# shield.net
KiCad netlist of a schematic drawn in EAGLE
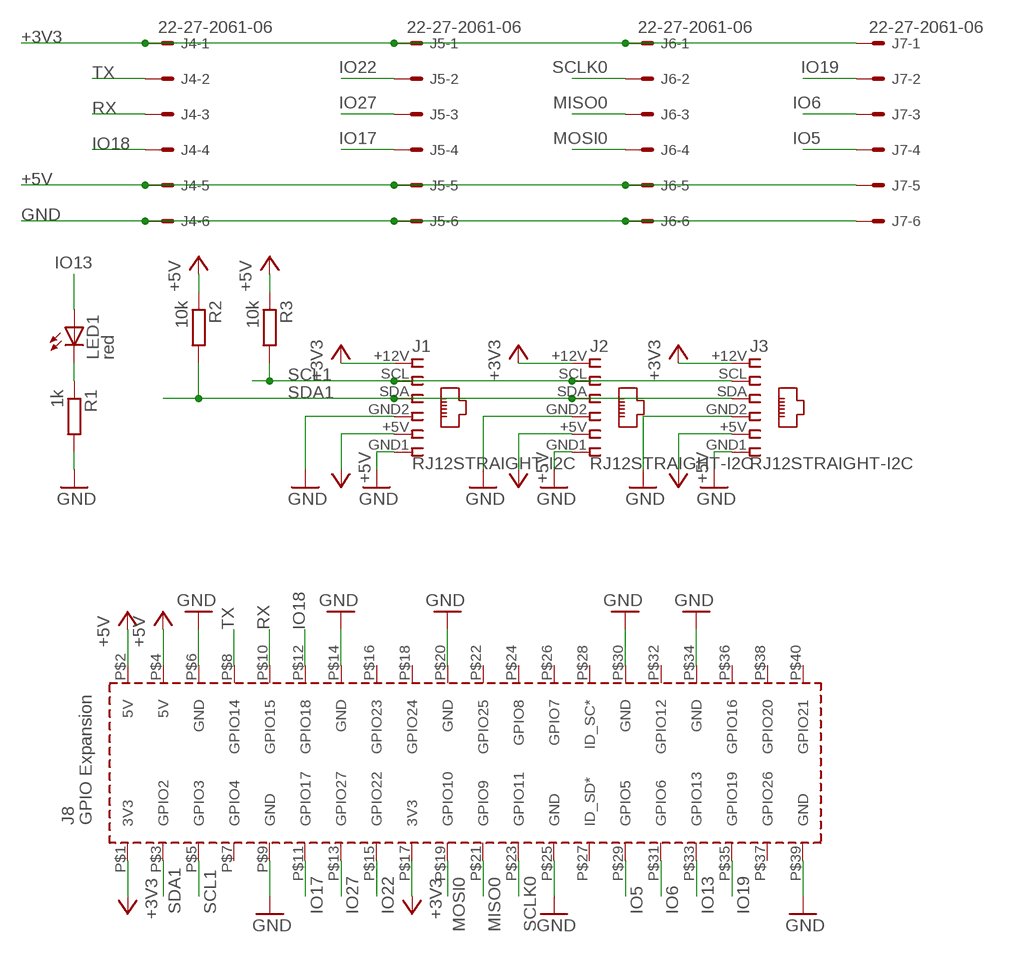
[diagram p0: schematic, sheet 1]

(export (version "E")
  (design (tool "Eeschema 10.0.6"))
  (components
    (comp (ref "J1")
      (value "RJ12STRAIGHT-I2C")
      (footprint "eagle-import:RJ12-STRAIGHT-I2C")
      (libsource (lib "eagle-import") (part "RJ12STRAIGHT-I2C"))
    )
    (comp (ref "J2")
      (value "RJ12STRAIGHT-I2C")
      (footprint "eagle-import:RJ12-STRAIGHT-I2C")
      (libsource (lib "eagle-import") (part "RJ12STRAIGHT-I2C"))
    )
    (comp (ref "J3")
      (value "RJ12STRAIGHT-I2C")
      (footprint "eagle-import:RJ12-STRAIGHT-I2C")
      (libsource (lib "eagle-import") (part "RJ12STRAIGHT-I2C"))
    )
    (comp (ref "J4")
      (value "22-27-2061-06")
      (footprint "eagle-import:6410-06")
      (fields (field (name "MF") "MOLEX"))
      (libsource (lib "eagle-import") (part "22-?-0627-2061"))
    )
    (comp (ref "J5")
      (value "22-27-2061-06")
      (footprint "eagle-import:6410-06")
      (fields (field (name "MF") "MOLEX"))
      (libsource (lib "eagle-import") (part "22-?-0627-2061"))
    )
    (comp (ref "J6")
      (value "22-27-2061-06")
      (footprint "eagle-import:6410-06")
      (fields (field (name "MF") "MOLEX"))
      (libsource (lib "eagle-import") (part "22-?-0627-2061"))
    )
    (comp (ref "J7")
      (value "22-27-2061-06")
      (footprint "eagle-import:6410-06")
      (fields (field (name "MF") "MOLEX"))
      (libsource (lib "eagle-import") (part "22-?-0627-2061"))
    )
    (comp (ref "LED1")
      (value "red")
      (footprint "eagle-import:SML0805")
      (libsource (lib "eagle-import") (part "LEDSML0805"))
    )
    (comp (ref "PCB1")
      (value "RPI3RPI3MIRROR")
      (footprint "eagle-import:RPI3MIRROR")
      (libsource (lib "eagle-import") (part "RPI3RPI3MIRROR"))
    )
    (comp (ref "R1")
      (value "1k")
      (footprint "eagle-import:R0805")
      (libsource (lib "eagle-import") (part "R-EU_R0805"))
    )
    (comp (ref "R2")
      (value "10k")
      (footprint "eagle-import:R0805")
      (libsource (lib "eagle-import") (part "R-EU_R0805"))
    )
    (comp (ref "R3")
      (value "10k")
      (footprint "eagle-import:R0805")
      (libsource (lib "eagle-import") (part "R-EU_R0805"))
    )
  )
  (nets
    (net (code "1") (name "+3V3") (class "Default")
      (node (ref "J1") (pin "+12V") (pinfunction "1_+12V") (pintype "bidirectional"))
      (node (ref "J2") (pin "+12V") (pinfunction "1_+12V") (pintype "bidirectional"))
      (node (ref "J3") (pin "+12V") (pinfunction "1_+12V") (pintype "bidirectional"))
      (node (ref "J4") (pin "1") (pinfunction "S_1") (pintype "passive"))
      (node (ref "J5") (pin "1") (pinfunction "S_1") (pintype "passive"))
      (node (ref "J6") (pin "1") (pinfunction "S_1") (pintype "passive"))
      (node (ref "J7") (pin "1") (pinfunction "S_1") (pintype "passive"))
      (node (ref "PCB1") (pin "P$1") (pinfunction "3V3_P$1") (pintype "bidirectional"))
      (node (ref "PCB1") (pin "P$17") (pinfunction "3V3_P$17") (pintype "bidirectional"))
    )
    (net (code "2") (name "+5V") (class "Default")
      (node (ref "J1") (pin "+5V") (pinfunction "5_+5V") (pintype "bidirectional"))
      (node (ref "J2") (pin "+5V") (pinfunction "5_+5V") (pintype "bidirectional"))
      (node (ref "J3") (pin "+5V") (pinfunction "5_+5V") (pintype "bidirectional"))
      (node (ref "J4") (pin "5") (pinfunction "S_5") (pintype "passive"))
      (node (ref "J5") (pin "5") (pinfunction "S_5") (pintype "passive"))
      (node (ref "J6") (pin "5") (pinfunction "S_5") (pintype "passive"))
      (node (ref "J7") (pin "5") (pinfunction "S_5") (pintype "passive"))
      (node (ref "PCB1") (pin "P$2") (pinfunction "5V_P$2") (pintype "bidirectional"))
      (node (ref "PCB1") (pin "P$4") (pinfunction "5V_P$4") (pintype "bidirectional"))
      (node (ref "R2") (pin "1") (pinfunction "1_1") (pintype "passive"))
      (node (ref "R3") (pin "1") (pinfunction "1_1") (pintype "passive"))
    )
    (net (code "3") (name "/IO5") (class "Default")
      (node (ref "J7") (pin "4") (pinfunction "S_4") (pintype "passive"))
      (node (ref "PCB1") (pin "P$29") (pinfunction "GPIO5_P$29") (pintype "bidirectional"))
    )
    (net (code "4") (name "/IO6") (class "Default")
      (node (ref "J7") (pin "3") (pinfunction "S_3") (pintype "passive"))
      (node (ref "PCB1") (pin "P$31") (pinfunction "GPIO6_P$31") (pintype "bidirectional"))
    )
    (net (code "5") (name "/IO13") (class "Default")
      (node (ref "LED1") (pin "A") (pinfunction "A_A") (pintype "passive"))
      (node (ref "PCB1") (pin "P$33") (pinfunction "GPIO13_P$33") (pintype "bidirectional"))
    )
    (net (code "6") (name "/IO17") (class "Default")
      (node (ref "J5") (pin "4") (pinfunction "S_4") (pintype "passive"))
      (node (ref "PCB1") (pin "P$11") (pinfunction "GPIO17_P$11") (pintype "bidirectional"))
    )
    (net (code "7") (name "/IO18") (class "Default")
      (node (ref "J4") (pin "4") (pinfunction "S_4") (pintype "passive"))
      (node (ref "PCB1") (pin "P$12") (pinfunction "GPIO18_P$12") (pintype "bidirectional"))
    )
    (net (code "8") (name "/IO19") (class "Default")
      (node (ref "J7") (pin "2") (pinfunction "S_2") (pintype "passive"))
      (node (ref "PCB1") (pin "P$35") (pinfunction "GPIO19_P$35") (pintype "bidirectional"))
    )
    (net (code "9") (name "/IO22") (class "Default")
      (node (ref "J5") (pin "2") (pinfunction "S_2") (pintype "passive"))
      (node (ref "PCB1") (pin "P$15") (pinfunction "GPIO22_P$15") (pintype "bidirectional"))
    )
    (net (code "10") (name "/IO27") (class "Default")
      (node (ref "J5") (pin "3") (pinfunction "S_3") (pintype "passive"))
      (node (ref "PCB1") (pin "P$13") (pinfunction "GPIO27_P$13") (pintype "bidirectional"))
    )
    (net (code "11") (name "/MISO0") (class "Default")
      (node (ref "J6") (pin "3") (pinfunction "S_3") (pintype "passive"))
      (node (ref "PCB1") (pin "P$21") (pinfunction "GPIO9_P$21") (pintype "bidirectional"))
    )
    (net (code "12") (name "/MOSI0") (class "Default")
      (node (ref "J6") (pin "4") (pinfunction "S_4") (pintype "passive"))
      (node (ref "PCB1") (pin "P$19") (pinfunction "GPIO10_P$19") (pintype "bidirectional"))
    )
    (net (code "13") (name "/RX") (class "Default")
      (node (ref "J4") (pin "3") (pinfunction "S_3") (pintype "passive"))
      (node (ref "PCB1") (pin "P$10") (pinfunction "GPIO15_P$10") (pintype "bidirectional"))
    )
    (net (code "14") (name "/SCL1") (class "Default")
      (node (ref "J1") (pin "SCL") (pinfunction "2_SCL") (pintype "bidirectional"))
      (node (ref "J2") (pin "SCL") (pinfunction "2_SCL") (pintype "bidirectional"))
      (node (ref "J3") (pin "SCL") (pinfunction "2_SCL") (pintype "bidirectional"))
      (node (ref "PCB1") (pin "P$5") (pinfunction "GPIO3_P$5") (pintype "bidirectional"))
      (node (ref "R3") (pin "2") (pinfunction "2_2") (pintype "passive"))
    )
    (net (code "15") (name "/SCLK0") (class "Default")
      (node (ref "J6") (pin "2") (pinfunction "S_2") (pintype "passive"))
      (node (ref "PCB1") (pin "P$23") (pinfunction "GPIO11_P$23") (pintype "bidirectional"))
    )
    (net (code "16") (name "/SDA1") (class "Default")
      (node (ref "J1") (pin "SDA") (pinfunction "3_SDA") (pintype "bidirectional"))
      (node (ref "J2") (pin "SDA") (pinfunction "3_SDA") (pintype "bidirectional"))
      (node (ref "J3") (pin "SDA") (pinfunction "3_SDA") (pintype "bidirectional"))
      (node (ref "PCB1") (pin "P$3") (pinfunction "GPIO2_P$3") (pintype "bidirectional"))
      (node (ref "R2") (pin "2") (pinfunction "2_2") (pintype "passive"))
    )
    (net (code "17") (name "/TX") (class "Default")
      (node (ref "J4") (pin "2") (pinfunction "S_2") (pintype "passive"))
      (node (ref "PCB1") (pin "P$8") (pinfunction "GPIO14_P$8") (pintype "bidirectional"))
    )
    (net (code "18") (name "GND") (class "Default")
      (node (ref "J1") (pin "GND1") (pinfunction "6_GND1") (pintype "bidirectional"))
      (node (ref "J1") (pin "GND2") (pinfunction "4_GND2") (pintype "bidirectional"))
      (node (ref "J2") (pin "GND1") (pinfunction "6_GND1") (pintype "bidirectional"))
      (node (ref "J2") (pin "GND2") (pinfunction "4_GND2") (pintype "bidirectional"))
      (node (ref "J3") (pin "GND1") (pinfunction "6_GND1") (pintype "bidirectional"))
      (node (ref "J3") (pin "GND2") (pinfunction "4_GND2") (pintype "bidirectional"))
      (node (ref "J4") (pin "6") (pinfunction "S_6") (pintype "passive"))
      (node (ref "J5") (pin "6") (pinfunction "S_6") (pintype "passive"))
      (node (ref "J6") (pin "6") (pinfunction "S_6") (pintype "passive"))
      (node (ref "J7") (pin "6") (pinfunction "S_6") (pintype "passive"))
      (node (ref "PCB1") (pin "P$14") (pinfunction "GND_P$14") (pintype "bidirectional"))
      (node (ref "PCB1") (pin "P$20") (pinfunction "GND_P$20") (pintype "bidirectional"))
      (node (ref "PCB1") (pin "P$25") (pinfunction "GND_P$25") (pintype "bidirectional"))
      (node (ref "PCB1") (pin "P$30") (pinfunction "GND_P$30") (pintype "bidirectional"))
      (node (ref "PCB1") (pin "P$34") (pinfunction "GND_P$34") (pintype "bidirectional"))
      (node (ref "PCB1") (pin "P$39") (pinfunction "GND_P$39") (pintype "bidirectional"))
      (node (ref "PCB1") (pin "P$6") (pinfunction "GND_P$6") (pintype "bidirectional"))
      (node (ref "PCB1") (pin "P$9") (pinfunction "GND_P$9") (pintype "bidirectional"))
      (node (ref "R1") (pin "2") (pinfunction "2_2") (pintype "passive"))
    )
    (net (code "19") (name "Net-(LED1-PadC)") (class "Default")
      (node (ref "LED1") (pin "C") (pinfunction "C_C") (pintype "passive"))
      (node (ref "R1") (pin "1") (pinfunction "1_1") (pintype "passive"))
    )
    (net (code "20") (name "unconnected-(PCB1-GPIO4-PadP$7)") (class "Default")
      (node (ref "PCB1") (pin "P$7") (pinfunction "GPIO4_P$7") (pintype "bidirectional"))
    )
    (net (code "21") (name "unconnected-(PCB1-GPIO7-PadP$26)") (class "Default")
      (node (ref "PCB1") (pin "P$26") (pinfunction "GPIO7_P$26") (pintype "bidirectional"))
    )
    (net (code "22") (name "unconnected-(PCB1-GPIO8-PadP$24)") (class "Default")
      (node (ref "PCB1") (pin "P$24") (pinfunction "GPIO8_P$24") (pintype "bidirectional"))
    )
    (net (code "23") (name "unconnected-(PCB1-GPIO12-PadP$32)") (class "Default")
      (node (ref "PCB1") (pin "P$32") (pinfunction "GPIO12_P$32") (pintype "bidirectional"))
    )
    (net (code "24") (name "unconnected-(PCB1-GPIO16-PadP$36)") (class "Default")
      (node (ref "PCB1") (pin "P$36") (pinfunction "GPIO16_P$36") (pintype "bidirectional"))
    )
    (net (code "25") (name "unconnected-(PCB1-GPIO20-PadP$38)") (class "Default")
      (node (ref "PCB1") (pin "P$38") (pinfunction "GPIO20_P$38") (pintype "bidirectional"))
    )
    (net (code "26") (name "unconnected-(PCB1-GPIO21-PadP$40)") (class "Default")
      (node (ref "PCB1") (pin "P$40") (pinfunction "GPIO21_P$40") (pintype "bidirectional"))
    )
    (net (code "27") (name "unconnected-(PCB1-GPIO23-PadP$16)") (class "Default")
      (node (ref "PCB1") (pin "P$16") (pinfunction "GPIO23_P$16") (pintype "bidirectional"))
    )
    (net (code "28") (name "unconnected-(PCB1-GPIO24-PadP$18)") (class "Default")
      (node (ref "PCB1") (pin "P$18") (pinfunction "GPIO24_P$18") (pintype "bidirectional"))
    )
    (net (code "29") (name "unconnected-(PCB1-GPIO25-PadP$22)") (class "Default")
      (node (ref "PCB1") (pin "P$22") (pinfunction "GPIO25_P$22") (pintype "bidirectional"))
    )
    (net (code "30") (name "unconnected-(PCB1-GPIO26-PadP$37)") (class "Default")
      (node (ref "PCB1") (pin "P$37") (pinfunction "GPIO26_P$37") (pintype "bidirectional"))
    )
    (net (code "31") (name "unconnected-(PCB1-ID_SC*-PadP$28)") (class "Default")
      (node (ref "PCB1") (pin "P$28") (pinfunction "ID_SC*_P$28") (pintype "bidirectional"))
    )
    (net (code "32") (name "unconnected-(PCB1-ID_SD*-PadP$27)") (class "Default")
      (node (ref "PCB1") (pin "P$27") (pinfunction "ID_SD*_P$27") (pintype "bidirectional"))
    )
  )
)
